# pure_energy.net
KiCad netlist of a schematic drawn in EAGLE
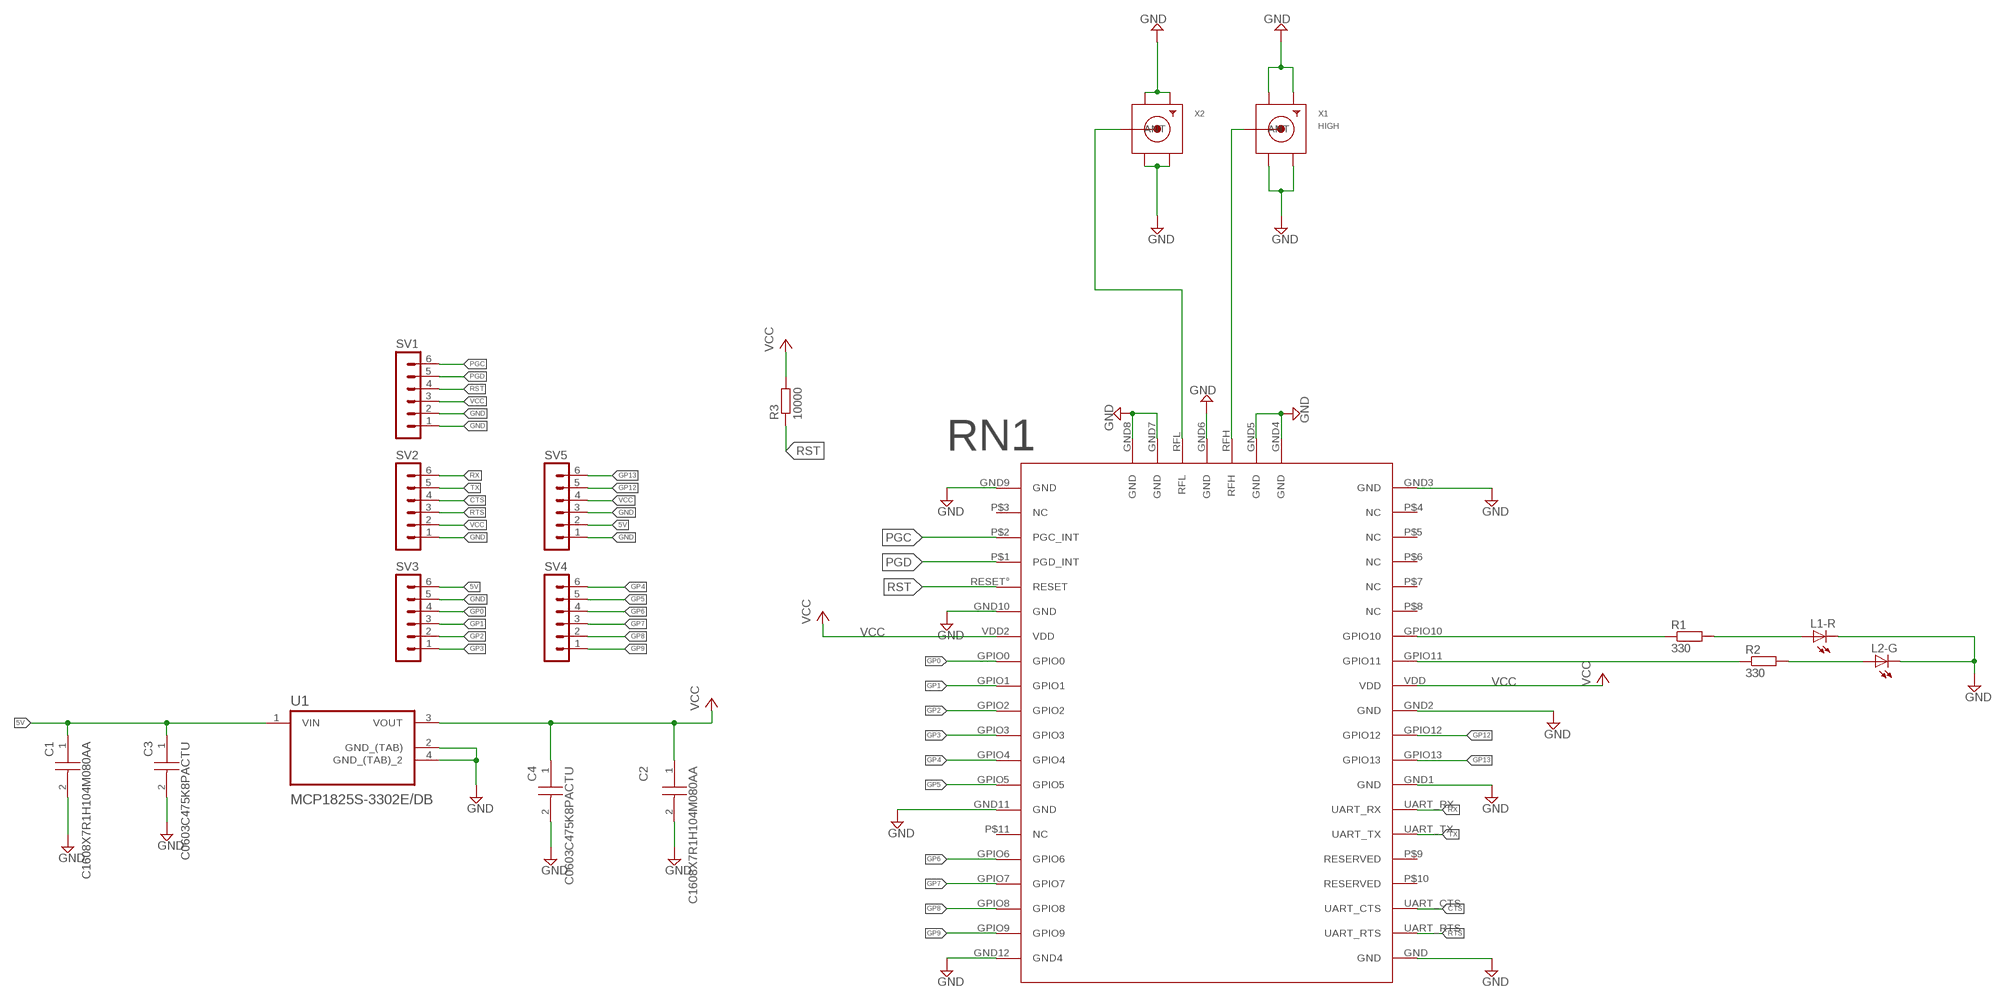
[diagram p0: schematic, sheet 1]

(export (version "E")
  (design (tool "Eeschema 10.0.6"))
  (components
    (comp (ref "C1")
      (value "C1608X7R1H104M080AA")
      (footprint "eagle-import:CAPC1608X80N")
      (fields (field (name "MOUSER_PART_NUMBER") "810-C1608X7R1H104M"))
      (libsource (lib "eagle-import") (part "C1608X7R1H104M080AA"))
    )
    (comp (ref "C2")
      (value "C1608X7R1H104M080AA")
      (footprint "eagle-import:CAPC1608X80N")
      (fields (field (name "MOUSER_PART_NUMBER") "810-C1608X7R1H104M"))
      (libsource (lib "eagle-import") (part "C1608X7R1H104M080AA"))
    )
    (comp (ref "C3")
      (value "C0603C475K8PACTU")
      (footprint "eagle-import:CAPC1608X85N")
      (fields (field (name "MOUSER_PART_NUMBER") "80-C0603C475K8P"))
      (libsource (lib "eagle-import") (part "C0603C475K8PACTU"))
    )
    (comp (ref "C4")
      (value "C0603C475K8PACTU")
      (footprint "eagle-import:CAPC1608X85N")
      (fields (field (name "MOUSER_PART_NUMBER") "80-C0603C475K8P"))
      (libsource (lib "eagle-import") (part "C0603C475K8PACTU"))
    )
    (comp (ref "L1-R")
      (value "LEDCHIP-LED0603")
      (footprint "eagle-import:CHIP-LED0603")
      (libsource (lib "eagle-import") (part "LEDCHIP-LED0603"))
    )
    (comp (ref "L2-G")
      (value "LEDCHIP-LED0603")
      (footprint "eagle-import:CHIP-LED0603")
      (libsource (lib "eagle-import") (part "LEDCHIP-LED0603"))
    )
    (comp (ref "R1")
      (value "330")
      (footprint "eagle-import:R0603")
      (libsource (lib "eagle-import") (part "R-EU_R0603"))
    )
    (comp (ref "R2")
      (value "330")
      (footprint "eagle-import:R0603")
      (libsource (lib "eagle-import") (part "R-EU_R0603"))
    )
    (comp (ref "R3")
      (value "10000")
      (footprint "eagle-import:R0603")
      (libsource (lib "eagle-import") (part "R-EU_R0603"))
    )
    (comp (ref "RN1")
      (value "NEW_RN2483")
      (footprint "eagle-import:NEW_RN2483")
      (libsource (lib "eagle-import") (part "NEW_RN2483"))
    )
    (comp (ref "SV1")
      (value "MA06-1")
      (footprint "eagle-import:MA06-1")
      (libsource (lib "eagle-import") (part "MA06-1"))
    )
    (comp (ref "SV2")
      (value "MA06-1")
      (footprint "eagle-import:MA06-1")
      (libsource (lib "eagle-import") (part "MA06-1"))
    )
    (comp (ref "SV3")
      (value "MA06-1")
      (footprint "eagle-import:MA06-1")
      (libsource (lib "eagle-import") (part "MA06-1"))
    )
    (comp (ref "SV4")
      (value "MA06-1")
      (footprint "eagle-import:MA06-1")
      (libsource (lib "eagle-import") (part "MA06-1"))
    )
    (comp (ref "SV5")
      (value "MA06-1")
      (footprint "eagle-import:MA06-1")
      (libsource (lib "eagle-import") (part "MA06-1"))
    )
    (comp (ref "U1")
      (value "MCP1825S-3302E/DB")
      (footprint "eagle-import:SOT230P700X180-4N")
      (fields (field (name "MF") "Microchip"))
      (libsource (lib "eagle-import") (part "MCP1825S-3302E/DB"))
    )
    (comp (ref "X1")
      (value "HIGH")
      (footprint "eagle-import:SMA_EDGELAUNCH")
      (libsource (lib "eagle-import") (part "SMACONNECTOR_EDGE"))
    )
    (comp (ref "X2")
      (value "SMACONNECTOR_EDGE")
      (footprint "eagle-import:SMA_EDGELAUNCH")
      (libsource (lib "eagle-import") (part "SMACONNECTOR_EDGE"))
    )
  )
  (nets
    (net (code "1") (name "5V") (class "Default")
      (node (ref "C1") (pin "1") (pinfunction "1_1") (pintype "bidirectional"))
      (node (ref "C3") (pin "1") (pinfunction "C1_1") (pintype "bidirectional"))
      (node (ref "SV3") (pin "6") (pinfunction "6_6") (pintype "passive"))
      (node (ref "SV5") (pin "2") (pinfunction "2_2") (pintype "passive"))
      (node (ref "U1") (pin "1") (pinfunction "VIN_1") (pintype "input"))
    )
    (net (code "2") (name "CTS") (class "Default")
      (node (ref "RN1") (pin "UART_CTS") (pinfunction "UART_CTS_UART_CTS") (pintype "bidirectional"))
      (node (ref "SV2") (pin "4") (pinfunction "4_4") (pintype "passive"))
    )
    (net (code "3") (name "GND") (class "Default")
      (node (ref "C1") (pin "2") (pinfunction "2_2") (pintype "bidirectional"))
      (node (ref "C2") (pin "2") (pinfunction "2_2") (pintype "bidirectional"))
      (node (ref "C3") (pin "2") (pinfunction "C2_2") (pintype "bidirectional"))
      (node (ref "C4") (pin "2") (pinfunction "C2_2") (pintype "bidirectional"))
      (node (ref "L1-R") (pin "C") (pinfunction "C_C") (pintype "passive"))
      (node (ref "L2-G") (pin "C") (pinfunction "C_C") (pintype "passive"))
      (node (ref "RN1") (pin "GND") (pinfunction "GND_GND") (pintype "bidirectional"))
      (node (ref "RN1") (pin "GND1") (pinfunction "GND_GND1") (pintype "bidirectional"))
      (node (ref "RN1") (pin "GND10") (pinfunction "GND_GND10") (pintype "bidirectional"))
      (node (ref "RN1") (pin "GND11") (pinfunction "GND_GND11") (pintype "bidirectional"))
      (node (ref "RN1") (pin "GND12") (pinfunction "GND4_GND12") (pintype "bidirectional"))
      (node (ref "RN1") (pin "GND2") (pinfunction "GND_GND2") (pintype "bidirectional"))
      (node (ref "RN1") (pin "GND3") (pinfunction "GND_GND3") (pintype "bidirectional"))
      (node (ref "RN1") (pin "GND4") (pinfunction "GND_GND4") (pintype "bidirectional"))
      (node (ref "RN1") (pin "GND5") (pinfunction "GND_GND5") (pintype "bidirectional"))
      (node (ref "RN1") (pin "GND6") (pinfunction "GND_GND6") (pintype "bidirectional"))
      (node (ref "RN1") (pin "GND7") (pinfunction "GND_GND7") (pintype "bidirectional"))
      (node (ref "RN1") (pin "GND8") (pinfunction "GND_GND8") (pintype "bidirectional"))
      (node (ref "RN1") (pin "GND9") (pinfunction "GND_GND9") (pintype "bidirectional"))
      (node (ref "SV1") (pin "1") (pinfunction "1_1") (pintype "passive"))
      (node (ref "SV1") (pin "2") (pinfunction "2_2") (pintype "passive"))
      (node (ref "SV2") (pin "1") (pinfunction "1_1") (pintype "passive"))
      (node (ref "SV3") (pin "5") (pinfunction "5_5") (pintype "passive"))
      (node (ref "SV5") (pin "1") (pinfunction "1_1") (pintype "passive"))
      (node (ref "SV5") (pin "3") (pinfunction "3_3") (pintype "passive"))
      (node (ref "U1") (pin "2") (pinfunction "GND_(TAB)_2") (pintype "power_in"))
      (node (ref "U1") (pin "4") (pinfunction "GND_(TAB)_2_4") (pintype "power_in"))
      (node (ref "X1") (pin "GND@1") (pinfunction "GND4_GND@1") (pintype "power_in"))
      (node (ref "X1") (pin "GND@2") (pinfunction "GND3_GND@2") (pintype "power_in"))
      (node (ref "X1") (pin "GND@3") (pinfunction "GND2_GND@3") (pintype "power_in"))
      (node (ref "X1") (pin "GND@4") (pinfunction "GND1_GND@4") (pintype "power_in"))
      (node (ref "X2") (pin "GND@1") (pinfunction "GND4_GND@1") (pintype "power_in"))
      (node (ref "X2") (pin "GND@2") (pinfunction "GND3_GND@2") (pintype "power_in"))
      (node (ref "X2") (pin "GND@3") (pinfunction "GND2_GND@3") (pintype "power_in"))
      (node (ref "X2") (pin "GND@4") (pinfunction "GND1_GND@4") (pintype "power_in"))
    )
    (net (code "4") (name "GP0") (class "Default")
      (node (ref "RN1") (pin "GPIO0") (pinfunction "GPIO0_GPIO0") (pintype "bidirectional"))
      (node (ref "SV3") (pin "4") (pinfunction "4_4") (pintype "passive"))
    )
    (net (code "5") (name "GP1") (class "Default")
      (node (ref "RN1") (pin "GPIO1") (pinfunction "GPIO1_GPIO1") (pintype "bidirectional"))
      (node (ref "SV3") (pin "3") (pinfunction "3_3") (pintype "passive"))
    )
    (net (code "6") (name "GP2") (class "Default")
      (node (ref "RN1") (pin "GPIO2") (pinfunction "GPIO2_GPIO2") (pintype "bidirectional"))
      (node (ref "SV3") (pin "2") (pinfunction "2_2") (pintype "passive"))
    )
    (net (code "7") (name "GP3") (class "Default")
      (node (ref "RN1") (pin "GPIO3") (pinfunction "GPIO3_GPIO3") (pintype "bidirectional"))
      (node (ref "SV3") (pin "1") (pinfunction "1_1") (pintype "passive"))
    )
    (net (code "8") (name "GP4") (class "Default")
      (node (ref "RN1") (pin "GPIO4") (pinfunction "GPIO4_GPIO4") (pintype "bidirectional"))
      (node (ref "SV4") (pin "6") (pinfunction "6_6") (pintype "passive"))
    )
    (net (code "9") (name "GP5") (class "Default")
      (node (ref "RN1") (pin "GPIO5") (pinfunction "GPIO5_GPIO5") (pintype "bidirectional"))
      (node (ref "SV4") (pin "5") (pinfunction "5_5") (pintype "passive"))
    )
    (net (code "10") (name "GP6") (class "Default")
      (node (ref "RN1") (pin "GPIO6") (pinfunction "GPIO6_GPIO6") (pintype "bidirectional"))
      (node (ref "SV4") (pin "4") (pinfunction "4_4") (pintype "passive"))
    )
    (net (code "11") (name "GP7") (class "Default")
      (node (ref "RN1") (pin "GPIO7") (pinfunction "GPIO7_GPIO7") (pintype "bidirectional"))
      (node (ref "SV4") (pin "3") (pinfunction "3_3") (pintype "passive"))
    )
    (net (code "12") (name "GP8") (class "Default")
      (node (ref "RN1") (pin "GPIO8") (pinfunction "GPIO8_GPIO8") (pintype "bidirectional"))
      (node (ref "SV4") (pin "2") (pinfunction "2_2") (pintype "passive"))
    )
    (net (code "13") (name "GP9") (class "Default")
      (node (ref "RN1") (pin "GPIO9") (pinfunction "GPIO9_GPIO9") (pintype "bidirectional"))
      (node (ref "SV4") (pin "1") (pinfunction "1_1") (pintype "passive"))
    )
    (net (code "14") (name "GP12") (class "Default")
      (node (ref "RN1") (pin "GPIO12") (pinfunction "GPIO12_GPIO12") (pintype "bidirectional"))
      (node (ref "SV5") (pin "5") (pinfunction "5_5") (pintype "passive"))
    )
    (net (code "15") (name "GP13") (class "Default")
      (node (ref "RN1") (pin "GPIO13") (pinfunction "GPIO13_GPIO13") (pintype "bidirectional"))
      (node (ref "SV5") (pin "6") (pinfunction "6_6") (pintype "passive"))
    )
    (net (code "16") (name "Net-(L1-R-PadA)") (class "Default")
      (node (ref "L1-R") (pin "A") (pinfunction "A_A") (pintype "passive"))
      (node (ref "R1") (pin "2") (pinfunction "2_2") (pintype "passive"))
    )
    (net (code "17") (name "Net-(L2-G-PadA)") (class "Default")
      (node (ref "L2-G") (pin "A") (pinfunction "A_A") (pintype "passive"))
      (node (ref "R2") (pin "2") (pinfunction "2_2") (pintype "passive"))
    )
    (net (code "18") (name "Net-(R1-Pad1)") (class "Default")
      (node (ref "R1") (pin "1") (pinfunction "1_1") (pintype "passive"))
      (node (ref "RN1") (pin "GPIO10") (pinfunction "GPIO10_GPIO10") (pintype "bidirectional"))
    )
    (net (code "19") (name "Net-(R2-Pad1)") (class "Default")
      (node (ref "R2") (pin "1") (pinfunction "1_1") (pintype "passive"))
      (node (ref "RN1") (pin "GPIO11") (pinfunction "GPIO11_GPIO11") (pintype "bidirectional"))
    )
    (net (code "20") (name "Net-(X1-ANT)") (class "Default")
      (node (ref "RN1") (pin "RFH") (pinfunction "RFH_RFH") (pintype "bidirectional"))
      (node (ref "X1") (pin "P") (pinfunction "ANT_P") (pintype "bidirectional"))
    )
    (net (code "21") (name "Net-(X2-ANT)") (class "Default")
      (node (ref "RN1") (pin "RFL") (pinfunction "RFL_RFL") (pintype "bidirectional"))
      (node (ref "X2") (pin "P") (pinfunction "ANT_P") (pintype "bidirectional"))
    )
    (net (code "22") (name "PGC") (class "Default")
      (node (ref "RN1") (pin "P$2") (pinfunction "PGC_INT_P$2") (pintype "bidirectional"))
      (node (ref "SV1") (pin "6") (pinfunction "6_6") (pintype "passive"))
    )
    (net (code "23") (name "PGD") (class "Default")
      (node (ref "RN1") (pin "P$1") (pinfunction "PGD_INT_P$1") (pintype "bidirectional"))
      (node (ref "SV1") (pin "5") (pinfunction "5_5") (pintype "passive"))
    )
    (net (code "24") (name "RST") (class "Default")
      (node (ref "R3") (pin "1") (pinfunction "1_1") (pintype "passive"))
      (node (ref "RN1") (pin "RESET°") (pinfunction "RESET_RESET°") (pintype "bidirectional"))
      (node (ref "SV1") (pin "4") (pinfunction "4_4") (pintype "passive"))
    )
    (net (code "25") (name "RTS") (class "Default")
      (node (ref "RN1") (pin "UART_RTS") (pinfunction "UART_RTS_UART_RTS") (pintype "bidirectional"))
      (node (ref "SV2") (pin "3") (pinfunction "3_3") (pintype "passive"))
    )
    (net (code "26") (name "RX") (class "Default")
      (node (ref "RN1") (pin "UART_RX") (pinfunction "UART_RX_UART_RX") (pintype "bidirectional"))
      (node (ref "SV2") (pin "6") (pinfunction "6_6") (pintype "passive"))
    )
    (net (code "27") (name "TX") (class "Default")
      (node (ref "RN1") (pin "UART_TX") (pinfunction "UART_TX_UART_TX") (pintype "bidirectional"))
      (node (ref "SV2") (pin "5") (pinfunction "5_5") (pintype "passive"))
    )
    (net (code "28") (name "VCC") (class "Default")
      (node (ref "C2") (pin "1") (pinfunction "1_1") (pintype "bidirectional"))
      (node (ref "C4") (pin "1") (pinfunction "C1_1") (pintype "bidirectional"))
      (node (ref "R3") (pin "2") (pinfunction "2_2") (pintype "passive"))
      (node (ref "RN1") (pin "VDD") (pinfunction "VDD_VDD") (pintype "bidirectional"))
      (node (ref "RN1") (pin "VDD2") (pinfunction "VDD_VDD2") (pintype "bidirectional"))
      (node (ref "SV1") (pin "3") (pinfunction "3_3") (pintype "passive"))
      (node (ref "SV2") (pin "2") (pinfunction "2_2") (pintype "passive"))
      (node (ref "SV5") (pin "4") (pinfunction "4_4") (pintype "passive"))
      (node (ref "U1") (pin "3") (pinfunction "VOUT_3") (pintype "output"))
    )
    (net (code "29") (name "unconnected-(RN1-NC-PadP$3)") (class "Default")
      (node (ref "RN1") (pin "P$3") (pinfunction "NC_P$3") (pintype "bidirectional"))
    )
    (net (code "30") (name "unconnected-(RN1-NC-PadP$4)") (class "Default")
      (node (ref "RN1") (pin "P$4") (pinfunction "NC_P$4") (pintype "bidirectional"))
    )
    (net (code "31") (name "unconnected-(RN1-NC-PadP$5)") (class "Default")
      (node (ref "RN1") (pin "P$5") (pinfunction "NC_P$5") (pintype "bidirectional"))
    )
    (net (code "32") (name "unconnected-(RN1-NC-PadP$6)") (class "Default")
      (node (ref "RN1") (pin "P$6") (pinfunction "NC_P$6") (pintype "bidirectional"))
    )
    (net (code "33") (name "unconnected-(RN1-NC-PadP$7)") (class "Default")
      (node (ref "RN1") (pin "P$7") (pinfunction "NC_P$7") (pintype "bidirectional"))
    )
    (net (code "34") (name "unconnected-(RN1-NC-PadP$8)") (class "Default")
      (node (ref "RN1") (pin "P$8") (pinfunction "NC_P$8") (pintype "bidirectional"))
    )
    (net (code "35") (name "unconnected-(RN1-NC-PadP$11)") (class "Default")
      (node (ref "RN1") (pin "P$11") (pinfunction "NC_P$11") (pintype "bidirectional"))
    )
    (net (code "36") (name "unconnected-(RN1-RESERVED-PadP$9)") (class "Default")
      (node (ref "RN1") (pin "P$9") (pinfunction "RESERVED_P$9") (pintype "bidirectional"))
    )
    (net (code "37") (name "unconnected-(RN1-RESERVED-PadP$10)") (class "Default")
      (node (ref "RN1") (pin "P$10") (pinfunction "RESERVED_P$10") (pintype "bidirectional"))
    )
  )
)
